# ESC1.net
KiCad netlist of a schematic drawn in Altium Designer
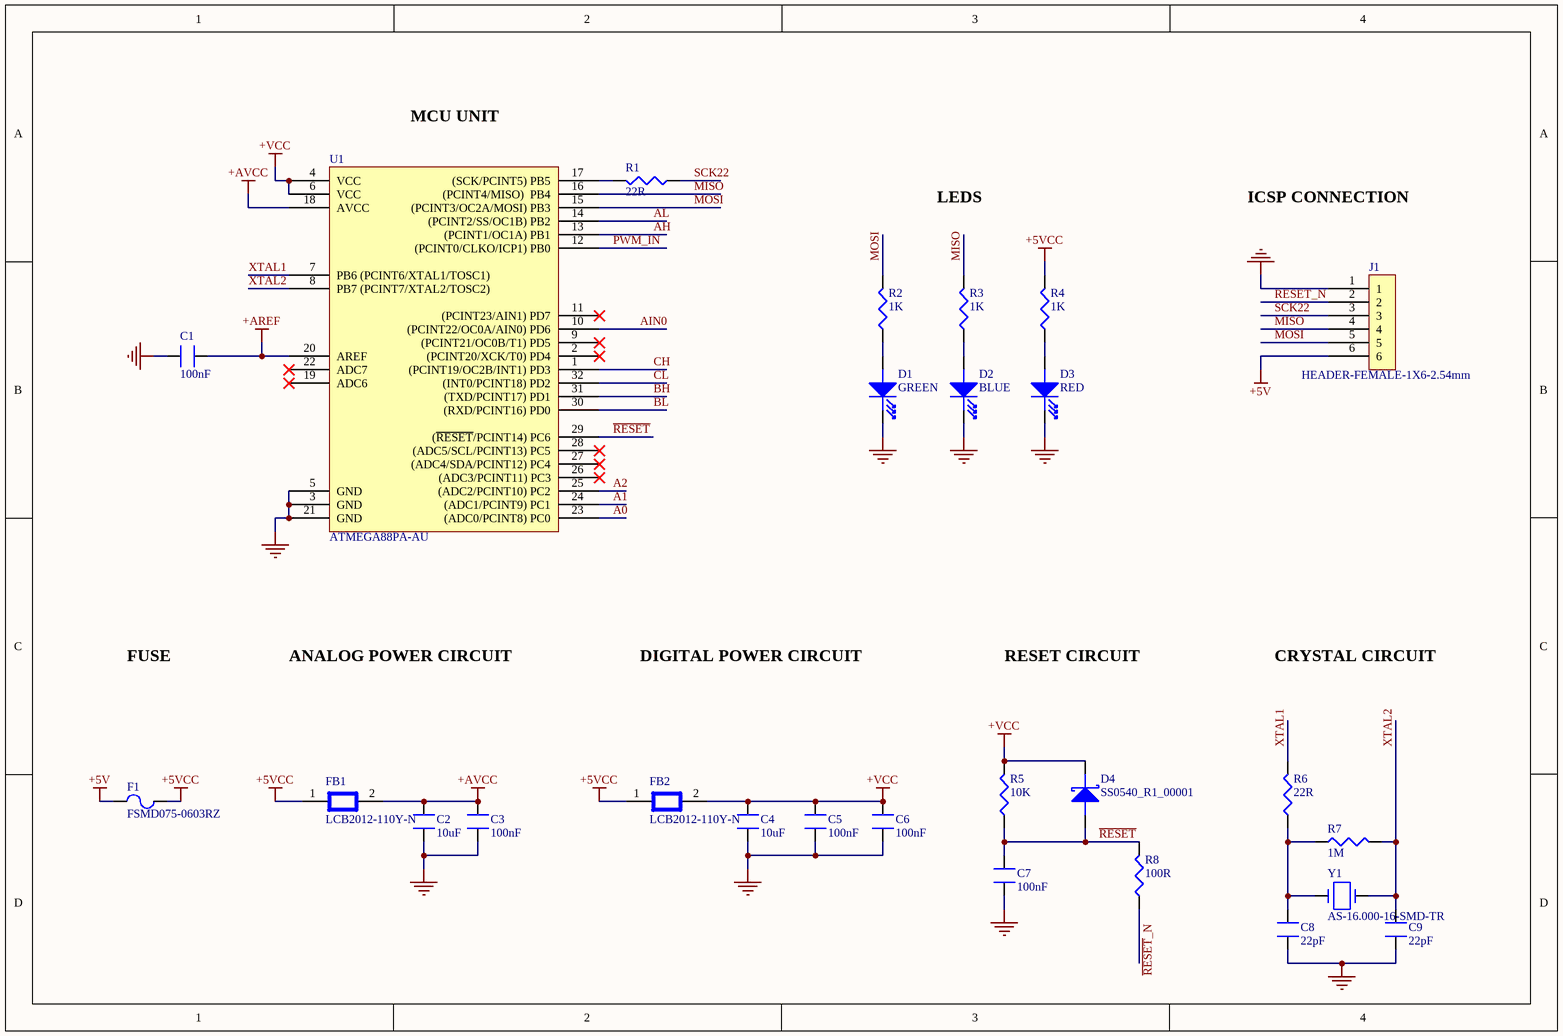
[diagram p0: ESC1.SchDoc]

(export (version "E")
  (design (tool "Eeschema 10.0.6"))
  (components
    (comp (ref "C1")
      (value "100nF")
      (footprint "Z0603")
      (description "Multi Layer Ceramic Capacitor (MLCC) / Cap Ceramic 0.1uF 50V X7R 10% Pad SMD 0603 125°C T/R")
      (fields
        (field (name "MANUFACTURER") "Samsung")
        (field (name "MANUFACTURER PART NUMBER") "CL10B104KB8NNNC")
      )
      (libsource (lib "ESClib1") (part "CL10B104KB8NNNC"))
    )
    (comp (ref "C2")
      (value "10uF")
      (footprint "Z0603")
      (description "Cap Ceramic 10uF 10V X5R 10% Pad SMD 0603 85C T/R")
      (fields
        (field (name "MANUFACTURER") "Samsung")
        (field (name "MANUFACTURER PART NUMBER") "CL10A106KP8NNNC")
      )
      (libsource (lib "ESClib1") (part "CL10A106KP8NNNC"))
    )
    (comp (ref "C3")
      (value "100nF")
      (footprint "Z0603")
      (description "Multi Layer Ceramic Capacitor (MLCC) / Cap Ceramic 0.1uF 50V X7R 10% Pad SMD 0603 125°C T/R")
      (fields
        (field (name "MANUFACTURER") "Samsung")
        (field (name "MANUFACTURER PART NUMBER") "CL10B104KB8NNNC")
      )
      (libsource (lib "ESClib1") (part "CL10B104KB8NNNC"))
    )
    (comp (ref "C4")
      (value "10uF")
      (footprint "Z0603")
      (description "Cap Ceramic 10uF 10V X5R 10% Pad SMD 0603 85C T/R")
      (fields
        (field (name "MANUFACTURER") "Samsung")
        (field (name "MANUFACTURER PART NUMBER") "CL10A106KP8NNNC")
      )
      (libsource (lib "ESClib1") (part "CL10A106KP8NNNC"))
    )
    (comp (ref "C5")
      (value "100nF")
      (footprint "Z0603")
      (description "Multi Layer Ceramic Capacitor (MLCC) / Cap Ceramic 0.1uF 50V X7R 10% Pad SMD 0603 125°C T/R")
      (fields
        (field (name "MANUFACTURER") "Samsung")
        (field (name "MANUFACTURER PART NUMBER") "CL10B104KB8NNNC")
      )
      (libsource (lib "ESClib1") (part "CL10B104KB8NNNC"))
    )
    (comp (ref "C6")
      (value "100nF")
      (footprint "Z0603")
      (description "Multi Layer Ceramic Capacitor (MLCC) / Cap Ceramic 0.1uF 50V X7R 10% Pad SMD 0603 125°C T/R")
      (fields
        (field (name "MANUFACTURER") "Samsung")
        (field (name "MANUFACTURER PART NUMBER") "CL10B104KB8NNNC")
      )
      (libsource (lib "ESClib1") (part "CL10B104KB8NNNC"))
    )
    (comp (ref "C7")
      (value "100nF")
      (footprint "Z0603")
      (description "Multi Layer Ceramic Capacitor (MLCC) / Cap Ceramic 0.1uF 50V X7R 10% Pad SMD 0603 125°C T/R")
      (fields
        (field (name "MANUFACTURER") "Samsung")
        (field (name "MANUFACTURER PART NUMBER") "CL10B104KB8NNNC")
      )
      (libsource (lib "ESClib1") (part "CL10B104KB8NNNC"))
    )
    (comp (ref "C8")
      (value "22pF")
      (footprint "Z0603")
      (description "Ceramic capacitor SMD-0603 22pF /50V NP0# J +-5%, Samsung, RoHS")
      (fields
        (field (name "MANUFACTURER") "Samsung")
        (field (name "MANUFACTURER PART NUMBER") "CL10C220JB8NNNC")
      )
      (libsource (lib "ESClib1") (part "CL10C220JB8NNNC"))
    )
    (comp (ref "C9")
      (value "22pF")
      (footprint "Z0603")
      (description "Ceramic capacitor SMD-0603 22pF /50V NP0# J +-5%, Samsung, RoHS")
      (fields
        (field (name "MANUFACTURER") "Samsung")
        (field (name "MANUFACTURER PART NUMBER") "CL10C220JB8NNNC")
      )
      (libsource (lib "ESClib1") (part "CL10C220JB8NNNC"))
    )
    (comp (ref "D1")
      (value "GREEN")
      (footprint "LED-0603")
      (libsource (lib "ESClib1") (part "HL-PST-1608U51GC"))
    )
    (comp (ref "D2")
      (value "BLUE")
      (footprint "LED-0603")
      (libsource (lib "ESClib1") (part "27-21/B7C-ZR1S1N/3C"))
    )
    (comp (ref "D3")
      (value "RED")
      (footprint "LED-0603")
      (description "0603 red led alingap 631nm-639nm water clear 18-180mcd 130d")
      (fields
        (field (name "MANUFACTURER") "Vishay Lite-On")
        (field (name "MANUFACTURER PART NUMBER") "LTST-C190KRKT")
      )
      (libsource (lib "ESClib1") (part "LTST-C190KRKT"))
    )
    (comp (ref "D4")
      (value "SS0540_R1_00001")
      (footprint "SOD-123")
      (description "Diode Schottky 40V 0.5A 2-Pin SOD-123 T/R")
      (fields (field (name "MANUFACTURER") "Pan Jit"))
      (libsource (lib "ESClib1") (part "SS0540_R1_00001"))
    )
    (comp (ref "F1")
      (value "FSMD075-0603RZ")
      (footprint "F-0603")
      (libsource (lib "ESClib1") (part "FSMD075-0603RZ"))
    )
    (comp (ref "FB1")
      (value "LCB2012-110Y-N")
      (footprint "C0805")
      (libsource (lib "ESClib1") (part "LCB2012-110Y-N"))
    )
    (comp (ref "FB2")
      (value "LCB2012-110Y-N")
      (footprint "C0805")
      (libsource (lib "ESClib1") (part "LCB2012-110Y-N"))
    )
    (comp (ref "J1")
      (value "HEADER-FEMALE-1X6-2.54mm")
      (footprint "FEMALE-1X6-2.54mm")
      (description "CONN HDR 6POS 0.1 GOLD PCB")
      (fields
        (field (name "MANUFACTURER") "Sullins")
        (field (name "MANUFACTURER PART NUMBER") "PPPC061LFBN-RC")
      )
      (libsource (lib "ESClib1") (part "PPPC061LFBN-RC"))
    )
    (comp (ref "R1")
      (value "22R")
      (footprint "Z0603")
      (description "MULTICOMP         MC0603SAF220JT5E            RESISTOR, THICK FILM, 22OHM, 100mW, 1%")
      (fields
        (field (name "MANUFACTURER") "Multicomp")
        (field (name "MANUFACTURER PART NUMBER") "MC0603SAF220JT5E")
      )
      (libsource (lib "ESClib1") (part "MC0603SAF220JT5E"))
    )
    (comp (ref "R2")
      (value "1K")
      (footprint "Z0603")
      (description "MULTICOMP - MC0603SAF1001T5E - THICK FILM RESISTOR, 1KOHM, 100mW, 1%")
      (fields
        (field (name "MANUFACTURER") "Multicomp")
        (field (name "MANUFACTURER PART NUMBER") "MC0603SAF1001T5E")
      )
      (libsource (lib "ESClib1") (part "MC0603SAF1001T5E"))
    )
    (comp (ref "R3")
      (value "1K")
      (footprint "Z0603")
      (description "MULTICOMP - MC0603SAF1001T5E - THICK FILM RESISTOR, 1KOHM, 100mW, 1%")
      (fields
        (field (name "MANUFACTURER") "Multicomp")
        (field (name "MANUFACTURER PART NUMBER") "MC0603SAF1001T5E")
      )
      (libsource (lib "ESClib1") (part "MC0603SAF1001T5E"))
    )
    (comp (ref "R4")
      (value "1K")
      (footprint "Z0603")
      (description "MULTICOMP - MC0603SAF1001T5E - THICK FILM RESISTOR, 1KOHM, 100mW, 1%")
      (fields
        (field (name "MANUFACTURER") "Multicomp")
        (field (name "MANUFACTURER PART NUMBER") "MC0603SAF1001T5E")
      )
      (libsource (lib "ESClib1") (part "MC0603SAF1001T5E"))
    )
    (comp (ref "R5") (value "10K") (footprint "Z0603") (libsource (lib "ESClib1") (part "CQ03SAF1002T5E")))
    (comp (ref "R6")
      (value "22R")
      (footprint "Z0603")
      (description "MULTICOMP         MC0603SAF220JT5E            RESISTOR, THICK FILM, 22OHM, 100mW, 1%")
      (fields
        (field (name "MANUFACTURER") "Multicomp")
        (field (name "MANUFACTURER PART NUMBER") "MC0603SAF220JT5E")
      )
      (libsource (lib "ESClib1") (part "MC0603SAF220JT5E"))
    )
    (comp (ref "R7")
      (value "1M")
      (footprint "Z0603")
      (description "Res General Purpose Thick Film 0603 1M Ohm 1% 1/10W ±100ppm/°C Molded T/R")
      (fields
        (field (name "MANUFACTURER") "Multicomp")
        (field (name "MANUFACTURER PART NUMBER") "MC0603SAF1004T5E")
      )
      (libsource (lib "ESClib1") (part "MC0603SAF1004T5E"))
    )
    (comp (ref "R8") (value "100R") (footprint "Z0603") (libsource (lib "ESClib1") (part "0603SAJ0101T5E")))
    (comp (ref "U1")
      (value "ATMEGA88PA-AU")
      (footprint "TQFP32(ATMEGA88)")
      (description "MCU 8-bit ATmega AVR RISC 8KB Flash 2.5V/3.3V/5V 32-Pin TQFP")
      (fields (field (name "MANUFACTURER") "Microchip / Atmel") (field (name "VOLTAGE") "5V"))
      (libsource (lib "ESClib1") (part "ATMEGA88PA-AU"))
    )
    (comp (ref "Y1")
      (value "AS-16.000-16-SMD-TR")
      (footprint "AS-16.000-16-SMD-TR")
      (description "AS-SMD Series 16 MHz ±30 ppm 16pF -20°C TO +70°C SMT Microprocessor Crystal")
      (fields (field (name "MANUFACTURER") "Raltron Electronics"))
      (libsource (lib "ESClib1") (part "AS-16.000-16-SMD-TR"))
    )
  )
  (nets
    (net (code "1") (name "+5V") (class "Default")
      (node (ref "F1") (pin "1") (pinfunction "1_1") (pintype "passive"))
      (node (ref "J1") (pin "6") (pinfunction "6_6") (pintype "passive"))
    )
    (net (code "2") (name "+5VCC") (class "Default")
      (node (ref "F1") (pin "2") (pinfunction "2_2") (pintype "passive"))
      (node (ref "FB1") (pin "1") (pinfunction "1_1") (pintype "passive"))
      (node (ref "FB2") (pin "1") (pinfunction "1_1") (pintype "passive"))
      (node (ref "R4") (pin "2") (pinfunction "2_2") (pintype "passive"))
    )
    (net (code "3") (name "+AREF") (class "Default")
      (node (ref "C1") (pin "1") (pinfunction "1_1") (pintype "passive"))
      (node (ref "U1") (pin "20") (pinfunction "AREF_20") (pintype "passive"))
    )
    (net (code "4") (name "+AVCC") (class "Default")
      (node (ref "C2") (pin "2") (pinfunction "2_2") (pintype "passive"))
      (node (ref "C3") (pin "2") (pinfunction "2_2") (pintype "passive"))
      (node (ref "FB1") (pin "2") (pinfunction "2_2") (pintype "passive"))
      (node (ref "U1") (pin "18") (pinfunction "AVCC_18") (pintype "passive"))
    )
    (net (code "5") (name "+VCC") (class "Default")
      (node (ref "C4") (pin "2") (pinfunction "2_2") (pintype "passive"))
      (node (ref "C5") (pin "2") (pinfunction "2_2") (pintype "passive"))
      (node (ref "C6") (pin "2") (pinfunction "2_2") (pintype "passive"))
      (node (ref "D4") (pin "1") (pinfunction "Cathode_1") (pintype "passive"))
      (node (ref "FB2") (pin "2") (pinfunction "2_2") (pintype "passive"))
      (node (ref "R5") (pin "2") (pinfunction "2_2") (pintype "passive"))
      (node (ref "U1") (pin "4") (pinfunction "VCC_4") (pintype "passive"))
      (node (ref "U1") (pin "6") (pinfunction "VCC_6") (pintype "passive"))
    )
    (net (code "6") (name "/A0") (class "Default")
      (node (ref "U1") (pin "23") (pinfunction "(ADC0/PCINT8)_PC0_23") (pintype "passive"))
    )
    (net (code "7") (name "/A1") (class "Default")
      (node (ref "U1") (pin "24") (pinfunction "(ADC1/PCINT9)_PC1_24") (pintype "passive"))
    )
    (net (code "8") (name "/A2") (class "Default")
      (node (ref "U1") (pin "25") (pinfunction "(ADC2/PCINT10)_PC2_25") (pintype "passive"))
    )
    (net (code "9") (name "/AH") (class "Default")
      (node (ref "U1") (pin "13") (pinfunction "(PCINT1/OC1A)_PB1_13") (pintype "passive"))
    )
    (net (code "10") (name "/AIN0") (class "Default")
      (node (ref "U1") (pin "10") (pinfunction "(PCINT22/OC0A/AIN0)_PD6_10") (pintype "passive"))
    )
    (net (code "11") (name "/AL") (class "Default")
      (node (ref "U1") (pin "14") (pinfunction "(PCINT2/SS/OC1B)_PB2_14") (pintype "passive"))
    )
    (net (code "12") (name "/BH") (class "Default")
      (node (ref "U1") (pin "31") (pinfunction "(TXD/PCINT17)_PD1_31") (pintype "passive"))
    )
    (net (code "13") (name "/BL") (class "Default")
      (node (ref "U1") (pin "30") (pinfunction "(RXD/PCINT16)_PD0_30") (pintype "passive"))
    )
    (net (code "14") (name "/CH") (class "Default")
      (node (ref "U1") (pin "1") (pinfunction "(PCINT19/OC2B/INT1)_PD3_1") (pintype "passive"))
    )
    (net (code "15") (name "/CL") (class "Default")
      (node (ref "U1") (pin "32") (pinfunction "(INT0/PCINT18)_PD2_32") (pintype "passive"))
    )
    (net (code "16") (name "/MISO") (class "Default")
      (node (ref "J1") (pin "4") (pinfunction "4_4") (pintype "passive"))
      (node (ref "R3") (pin "2") (pinfunction "2_2") (pintype "passive"))
      (node (ref "U1") (pin "16") (pinfunction "(PCINT4/MISO)__PB4_16") (pintype "passive"))
    )
    (net (code "17") (name "/MOSI") (class "Default")
      (node (ref "J1") (pin "5") (pinfunction "5_5") (pintype "passive"))
      (node (ref "R2") (pin "2") (pinfunction "2_2") (pintype "passive"))
      (node (ref "U1") (pin "15") (pinfunction "(PCINT3/OC2A/MOSI)_PB3_15") (pintype "passive"))
    )
    (net (code "18") (name "/PWM_IN") (class "Default")
      (node (ref "U1") (pin "12") (pinfunction "(PCINT0/CLKO/ICP1)_PB0_12") (pintype "passive"))
    )
    (net (code "19") (name "/SCK22") (class "Default")
      (node (ref "J1") (pin "3") (pinfunction "3_3") (pintype "passive"))
      (node (ref "R1") (pin "1") (pinfunction "1_1") (pintype "passive"))
    )
    (net (code "20") (name "/XTAL1") (class "Default")
      (node (ref "R6") (pin "2") (pinfunction "2_2") (pintype "passive"))
      (node (ref "U1") (pin "7") (pinfunction "PB6_(PCINT6/XTAL1/TOSC1)_7") (pintype "passive"))
    )
    (net (code "21") (name "/XTAL2") (class "Default")
      (node (ref "C9") (pin "1") (pinfunction "1_1") (pintype "passive"))
      (node (ref "R7") (pin "2") (pinfunction "2_2") (pintype "passive"))
      (node (ref "U1") (pin "8") (pinfunction "PB7_(PCINT7/XTAL2/TOSC2)_8") (pintype "passive"))
      (node (ref "Y1") (pin "2") (pinfunction "2_2") (pintype "passive"))
    )
    (net (code "22") (name "/~{RESET}") (class "Default")
      (node (ref "C7") (pin "2") (pinfunction "2_2") (pintype "passive"))
      (node (ref "D4") (pin "2") (pinfunction "Anode_2") (pintype "passive"))
      (node (ref "R5") (pin "1") (pinfunction "1_1") (pintype "passive"))
      (node (ref "R8") (pin "2") (pinfunction "2_2") (pintype "passive"))
      (node (ref "U1") (pin "29") (pinfunction "(~{RESET}/PCINT14)_PC6_29") (pintype "passive"))
    )
    (net (code "23") (name "/~{RESET}_N") (class "Default")
      (node (ref "J1") (pin "2") (pinfunction "2_2") (pintype "passive"))
      (node (ref "R8") (pin "1") (pinfunction "1_1") (pintype "passive"))
    )
    (net (code "24") (name "GND") (class "Default")
      (node (ref "C1") (pin "2") (pinfunction "2_2") (pintype "passive"))
      (node (ref "C2") (pin "1") (pinfunction "1_1") (pintype "passive"))
      (node (ref "C3") (pin "1") (pinfunction "1_1") (pintype "passive"))
      (node (ref "C4") (pin "1") (pinfunction "1_1") (pintype "passive"))
      (node (ref "C5") (pin "1") (pinfunction "1_1") (pintype "passive"))
      (node (ref "C6") (pin "1") (pinfunction "1_1") (pintype "passive"))
      (node (ref "C7") (pin "1") (pinfunction "1_1") (pintype "passive"))
      (node (ref "C8") (pin "2") (pinfunction "2_2") (pintype "passive"))
      (node (ref "C9") (pin "2") (pinfunction "2_2") (pintype "passive"))
      (node (ref "D1") (pin "1") (pinfunction "Cathode_1") (pintype "passive"))
      (node (ref "D2") (pin "1") (pinfunction "Cathode_1") (pintype "passive"))
      (node (ref "D3") (pin "1") (pinfunction "Cathode_1") (pintype "passive"))
      (node (ref "J1") (pin "1") (pinfunction "1_1") (pintype "passive"))
      (node (ref "U1") (pin "21") (pinfunction "GND_21") (pintype "passive"))
      (node (ref "U1") (pin "3") (pinfunction "GND_3") (pintype "passive"))
      (node (ref "U1") (pin "5") (pinfunction "GND_5") (pintype "passive"))
    )
    (net (code "25") (name "Net-(C8-Pad1)") (class "Default")
      (node (ref "C8") (pin "1") (pinfunction "1_1") (pintype "passive"))
      (node (ref "R6") (pin "1") (pinfunction "1_1") (pintype "passive"))
      (node (ref "R7") (pin "1") (pinfunction "1_1") (pintype "passive"))
      (node (ref "Y1") (pin "1") (pinfunction "1_1") (pintype "passive"))
    )
    (net (code "26") (name "Net-(D1-Anode)") (class "Default")
      (node (ref "D1") (pin "2") (pinfunction "Anode_2") (pintype "passive"))
      (node (ref "R2") (pin "1") (pinfunction "1_1") (pintype "passive"))
    )
    (net (code "27") (name "Net-(D2-Anode)") (class "Default")
      (node (ref "D2") (pin "2") (pinfunction "Anode_2") (pintype "passive"))
      (node (ref "R3") (pin "1") (pinfunction "1_1") (pintype "passive"))
    )
    (net (code "28") (name "Net-(D3-Anode)") (class "Default")
      (node (ref "D3") (pin "2") (pinfunction "Anode_2") (pintype "passive"))
      (node (ref "R4") (pin "1") (pinfunction "1_1") (pintype "passive"))
    )
    (net (code "29") (name "Net-(U1-(SCK{slash}PCINT5)_PB5)") (class "Default")
      (node (ref "R1") (pin "2") (pinfunction "2_2") (pintype "passive"))
      (node (ref "U1") (pin "17") (pinfunction "(SCK/PCINT5)_PB5_17") (pintype "passive"))
    )
    (net (code "30") (name "unconnected-(U1-(ADC3{slash}PCINT11)_PC3-Pad26)") (class "Default")
      (node (ref "U1") (pin "26") (pinfunction "(ADC3/PCINT11)_PC3_26") (pintype "passive+no_connect"))
    )
    (net (code "31") (name "unconnected-(U1-(ADC4{slash}SDA{slash}PCINT12)_PC4-Pad27)") (class "Default")
      (node (ref "U1") (pin "27") (pinfunction "(ADC4/SDA/PCINT12)_PC4_27") (pintype "passive+no_connect"))
    )
    (net (code "32") (name "unconnected-(U1-(ADC5{slash}SCL{slash}PCINT13)_PC5-Pad28)") (class "Default")
      (node (ref "U1") (pin "28") (pinfunction "(ADC5/SCL/PCINT13)_PC5_28") (pintype "passive+no_connect"))
    )
    (net (code "33") (name "unconnected-(U1-(PCINT20{slash}XCK{slash}T0)_PD4-Pad2)") (class "Default")
      (node (ref "U1") (pin "2") (pinfunction "(PCINT20/XCK/T0)_PD4_2") (pintype "passive+no_connect"))
    )
    (net (code "34") (name "unconnected-(U1-(PCINT21{slash}OC0B{slash}T1)_PD5-Pad9)") (class "Default")
      (node (ref "U1") (pin "9") (pinfunction "(PCINT21/OC0B/T1)_PD5_9") (pintype "passive+no_connect"))
    )
    (net (code "35") (name "unconnected-(U1-(PCINT23{slash}AIN1)_PD7-Pad11)") (class "Default")
      (node (ref "U1") (pin "11") (pinfunction "(PCINT23/AIN1)_PD7_11") (pintype "passive+no_connect"))
    )
    (net (code "36") (name "unconnected-(U1-ADC6-Pad19)") (class "Default")
      (node (ref "U1") (pin "19") (pinfunction "ADC6_19") (pintype "passive+no_connect"))
    )
    (net (code "37") (name "unconnected-(U1-ADC7-Pad22)") (class "Default")
      (node (ref "U1") (pin "22") (pinfunction "ADC7_22") (pintype "passive+no_connect"))
    )
  )
)
